# M652A.net
KiCad netlist of a schematic drawn in EAGLE
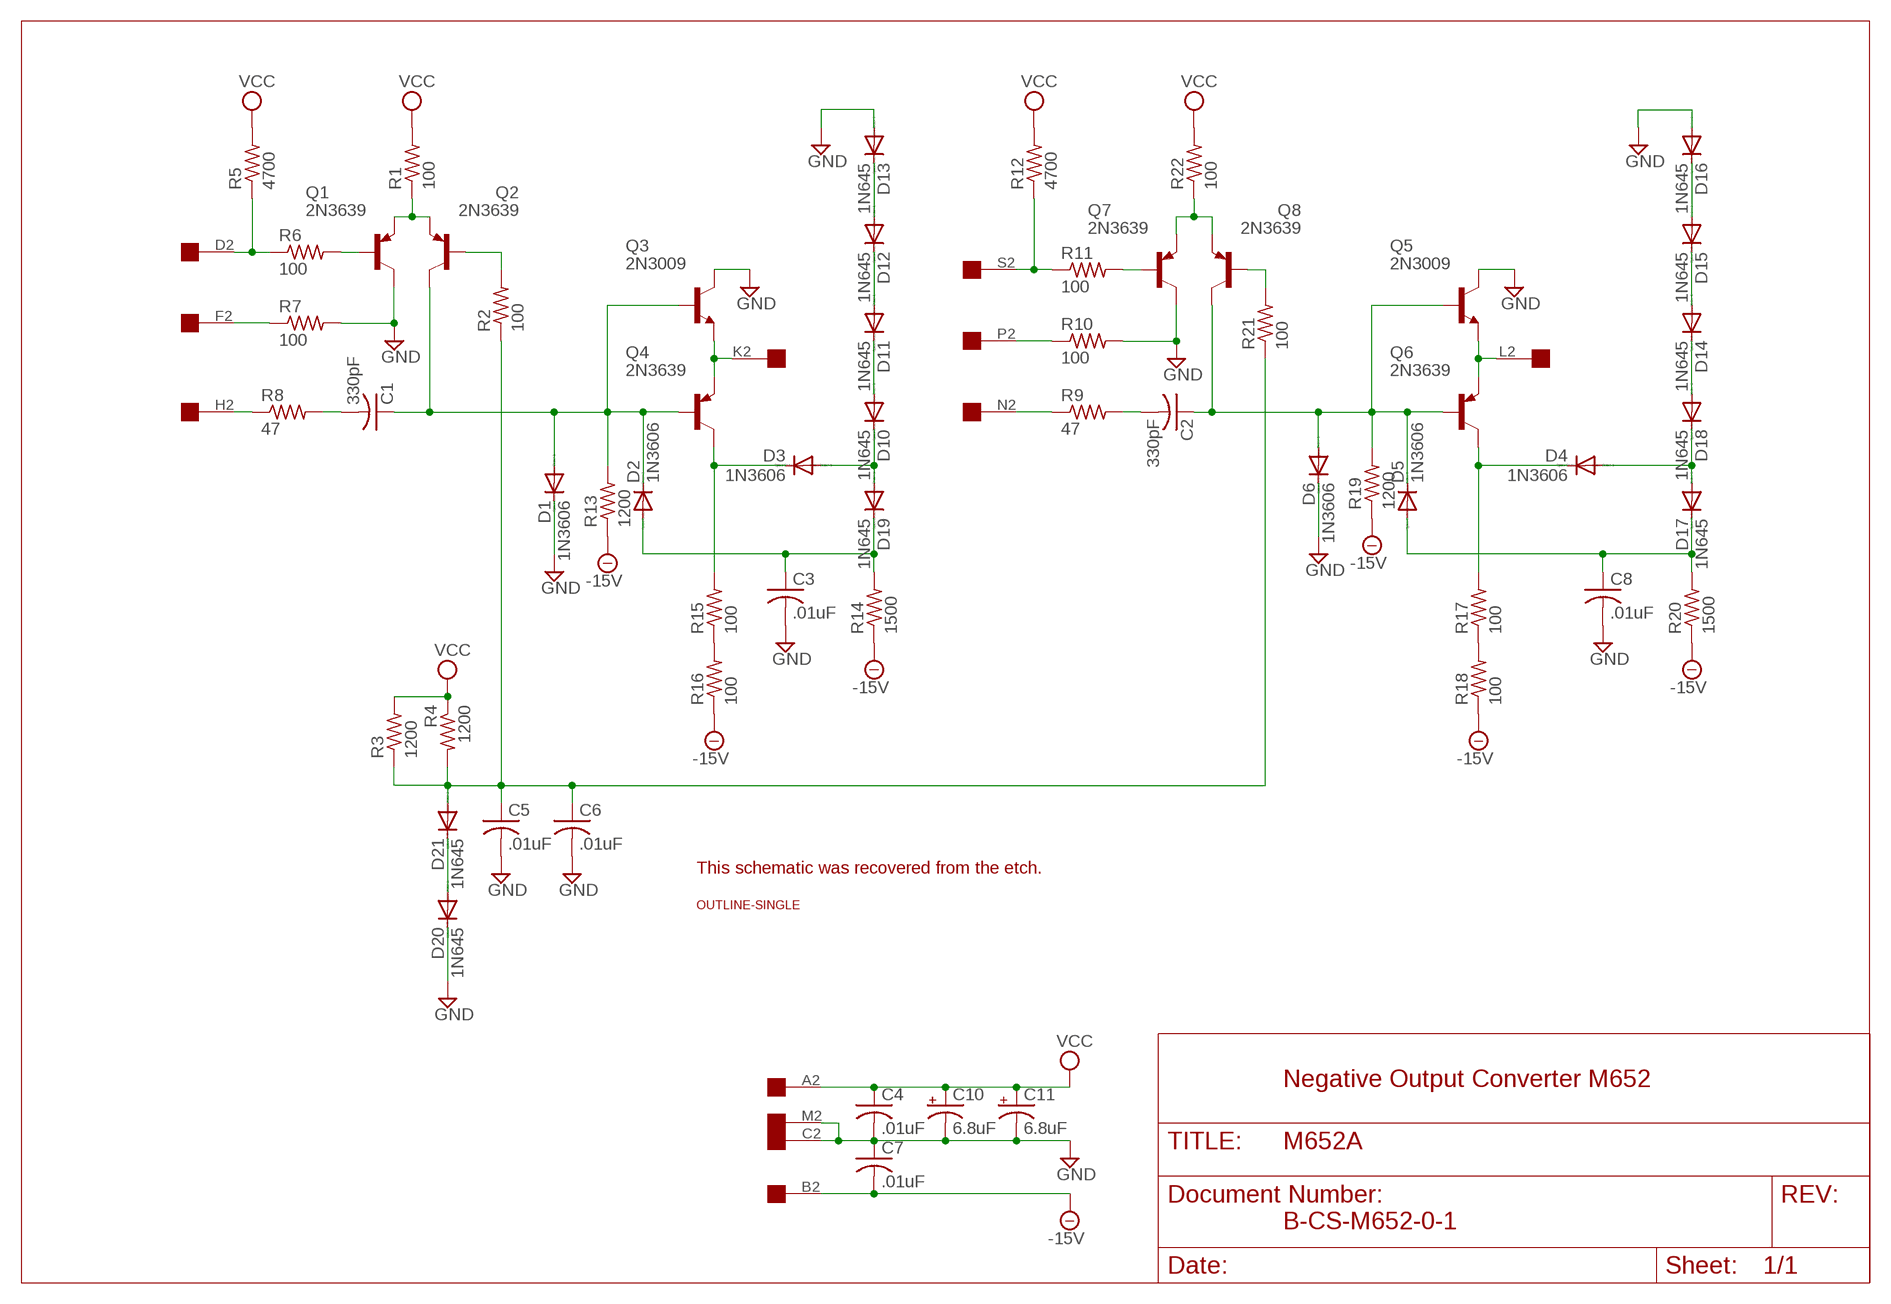
[diagram p0: schematic, sheet 1]

(export (version "E")
  (design (tool "Eeschema 10.0.6"))
  (components
    (comp (ref "C1")
      (value "330pF")
      (footprint "eagle-import:C150-054X183")
      (libsource (lib "eagle-import") (part "C-US150-054X183"))
    )
    (comp (ref "C2")
      (value "330pF")
      (footprint "eagle-import:C150-054X183")
      (libsource (lib "eagle-import") (part "C-US150-054X183"))
    )
    (comp (ref "C3")
      (value ".01uF")
      (footprint "eagle-import:C050-025X075")
      (libsource (lib "eagle-import") (part "C-US050-025X075"))
    )
    (comp (ref "C4")
      (value ".01uF")
      (footprint "eagle-import:C050-025X075")
      (libsource (lib "eagle-import") (part "C-US050-025X075"))
    )
    (comp (ref "C5")
      (value ".01uF")
      (footprint "eagle-import:C050-025X075")
      (libsource (lib "eagle-import") (part "C-US050-025X075"))
    )
    (comp (ref "C6")
      (value ".01uF")
      (footprint "eagle-import:C050-025X075")
      (libsource (lib "eagle-import") (part "C-US050-025X075"))
    )
    (comp (ref "C7")
      (value ".01uF")
      (footprint "eagle-import:C050-025X075")
      (libsource (lib "eagle-import") (part "C-US050-025X075"))
    )
    (comp (ref "C8")
      (value ".01uF")
      (footprint "eagle-import:C050-025X075")
      (libsource (lib "eagle-import") (part "C-US050-025X075"))
    )
    (comp (ref "C10")
      (value "6.8uF")
      (footprint "eagle-import:E12-4")
      (libsource (lib "eagle-import") (part "CPOL-USE12-4AXIAL"))
    )
    (comp (ref "C11")
      (value "6.8uF")
      (footprint "eagle-import:E12-4")
      (libsource (lib "eagle-import") (part "CPOL-USE12-4AXIAL"))
    )
    (comp (ref "D1")
      (value "1N3606")
      (footprint "eagle-import:DO35-10")
      (libsource (lib "eagle-import") (part "1N4148DO35-10"))
    )
    (comp (ref "D2")
      (value "1N3606")
      (footprint "eagle-import:DO35-10")
      (libsource (lib "eagle-import") (part "1N4148DO35-10"))
    )
    (comp (ref "D3")
      (value "1N3606")
      (footprint "eagle-import:DO35-10")
      (libsource (lib "eagle-import") (part "1N4148DO35-10"))
    )
    (comp (ref "D4")
      (value "1N3606")
      (footprint "eagle-import:DO35-10")
      (libsource (lib "eagle-import") (part "1N4148DO35-10"))
    )
    (comp (ref "D5")
      (value "1N3606")
      (footprint "eagle-import:DO35-10")
      (libsource (lib "eagle-import") (part "1N4148DO35-10"))
    )
    (comp (ref "D6")
      (value "1N3606")
      (footprint "eagle-import:DO35-10")
      (libsource (lib "eagle-import") (part "1N4148DO35-10"))
    )
    (comp (ref "D10")
      (value "1N645")
      (footprint "eagle-import:DO35-10")
      (libsource (lib "eagle-import") (part "1N4148DO35-10"))
    )
    (comp (ref "D11")
      (value "1N645")
      (footprint "eagle-import:DO35-10")
      (libsource (lib "eagle-import") (part "1N4148DO35-10"))
    )
    (comp (ref "D12")
      (value "1N645")
      (footprint "eagle-import:DO35-10")
      (libsource (lib "eagle-import") (part "1N4148DO35-10"))
    )
    (comp (ref "D13")
      (value "1N645")
      (footprint "eagle-import:DO35-10")
      (libsource (lib "eagle-import") (part "1N4148DO35-10"))
    )
    (comp (ref "D14")
      (value "1N645")
      (footprint "eagle-import:DO35-10")
      (libsource (lib "eagle-import") (part "1N4148DO35-10"))
    )
    (comp (ref "D15")
      (value "1N645")
      (footprint "eagle-import:DO35-10")
      (libsource (lib "eagle-import") (part "1N4148DO35-10"))
    )
    (comp (ref "D16")
      (value "1N645")
      (footprint "eagle-import:DO35-10")
      (libsource (lib "eagle-import") (part "1N4148DO35-10"))
    )
    (comp (ref "D17")
      (value "1N645")
      (footprint "eagle-import:DO35-10")
      (libsource (lib "eagle-import") (part "1N4148DO35-10"))
    )
    (comp (ref "D18")
      (value "1N645")
      (footprint "eagle-import:DO35-10")
      (libsource (lib "eagle-import") (part "1N4148DO35-10"))
    )
    (comp (ref "D19")
      (value "1N645")
      (footprint "eagle-import:DO35-10")
      (libsource (lib "eagle-import") (part "1N4148DO35-10"))
    )
    (comp (ref "D20")
      (value "1N645")
      (footprint "eagle-import:DO35-10")
      (libsource (lib "eagle-import") (part "1N4148DO35-10"))
    )
    (comp (ref "D21")
      (value "1N645")
      (footprint "eagle-import:DO35-10")
      (libsource (lib "eagle-import") (part "1N4148DO35-10"))
    )
    (comp (ref "Q1")
      (value "2N3639")
      (footprint "eagle-import:TO39")
      (libsource (lib "eagle-import") (part "2N5415"))
    )
    (comp (ref "Q2")
      (value "2N3639")
      (footprint "eagle-import:TO39")
      (libsource (lib "eagle-import") (part "2N5415"))
    )
    (comp (ref "Q3")
      (value "2N3009")
      (footprint "eagle-import:TO5")
      (libsource (lib "eagle-import") (part "2N2219"))
    )
    (comp (ref "Q4")
      (value "2N3639")
      (footprint "eagle-import:TO39")
      (libsource (lib "eagle-import") (part "2N5415"))
    )
    (comp (ref "Q5")
      (value "2N3009")
      (footprint "eagle-import:TO5")
      (libsource (lib "eagle-import") (part "2N2219"))
    )
    (comp (ref "Q6")
      (value "2N3639")
      (footprint "eagle-import:TO39")
      (libsource (lib "eagle-import") (part "2N5415"))
    )
    (comp (ref "Q7")
      (value "2N3639")
      (footprint "eagle-import:TO39")
      (libsource (lib "eagle-import") (part "2N5415"))
    )
    (comp (ref "Q8")
      (value "2N3639")
      (footprint "eagle-import:TO39")
      (libsource (lib "eagle-import") (part "2N5415"))
    )
    (comp (ref "R1")
      (value "100")
      (footprint "eagle-import:0207_10")
      (libsource (lib "eagle-import") (part "R-US_0207/10"))
    )
    (comp (ref "R2")
      (value "100")
      (footprint "eagle-import:0207_10")
      (libsource (lib "eagle-import") (part "R-US_0207/10"))
    )
    (comp (ref "R3")
      (value "1200")
      (footprint "eagle-import:0207_10")
      (libsource (lib "eagle-import") (part "R-US_0207/10"))
    )
    (comp (ref "R4")
      (value "1200")
      (footprint "eagle-import:0207_10")
      (libsource (lib "eagle-import") (part "R-US_0207/10"))
    )
    (comp (ref "R5")
      (value "4700")
      (footprint "eagle-import:0207_10")
      (libsource (lib "eagle-import") (part "R-US_0207/10"))
    )
    (comp (ref "R6")
      (value "100")
      (footprint "eagle-import:0207_10")
      (libsource (lib "eagle-import") (part "R-US_0207/10"))
    )
    (comp (ref "R7")
      (value "100")
      (footprint "eagle-import:0207_10")
      (libsource (lib "eagle-import") (part "R-US_0207/10"))
    )
    (comp (ref "R8")
      (value "47")
      (footprint "eagle-import:0207_10")
      (libsource (lib "eagle-import") (part "R-US_0207/10"))
    )
    (comp (ref "R9")
      (value "47")
      (footprint "eagle-import:0207_10")
      (libsource (lib "eagle-import") (part "R-US_0207/10"))
    )
    (comp (ref "R10")
      (value "100")
      (footprint "eagle-import:0207_10")
      (libsource (lib "eagle-import") (part "R-US_0207/10"))
    )
    (comp (ref "R11")
      (value "100")
      (footprint "eagle-import:0207_10")
      (libsource (lib "eagle-import") (part "R-US_0207/10"))
    )
    (comp (ref "R12")
      (value "4700")
      (footprint "eagle-import:0207_10")
      (libsource (lib "eagle-import") (part "R-US_0207/10"))
    )
    (comp (ref "R13")
      (value "1200")
      (footprint "eagle-import:0207_10")
      (libsource (lib "eagle-import") (part "R-US_0207/10"))
    )
    (comp (ref "R14")
      (value "1500")
      (footprint "eagle-import:0207_10")
      (libsource (lib "eagle-import") (part "R-US_0207/10"))
    )
    (comp (ref "R15")
      (value "100")
      (footprint "eagle-import:0207_10")
      (libsource (lib "eagle-import") (part "R-US_0207/10"))
    )
    (comp (ref "R16")
      (value "100")
      (footprint "eagle-import:0207_10")
      (libsource (lib "eagle-import") (part "R-US_0207/10"))
    )
    (comp (ref "R17")
      (value "100")
      (footprint "eagle-import:0207_10")
      (libsource (lib "eagle-import") (part "R-US_0207/10"))
    )
    (comp (ref "R18")
      (value "100")
      (footprint "eagle-import:0207_10")
      (libsource (lib "eagle-import") (part "R-US_0207/10"))
    )
    (comp (ref "R19")
      (value "1200")
      (footprint "eagle-import:0207_10")
      (libsource (lib "eagle-import") (part "R-US_0207/10"))
    )
    (comp (ref "R20")
      (value "1500")
      (footprint "eagle-import:0207_10")
      (libsource (lib "eagle-import") (part "R-US_0207/10"))
    )
    (comp (ref "R21")
      (value "100")
      (footprint "eagle-import:0207_10")
      (libsource (lib "eagle-import") (part "R-US_0207/10"))
    )
    (comp (ref "R22")
      (value "100")
      (footprint "eagle-import:0207_10")
      (libsource (lib "eagle-import") (part "R-US_0207/10"))
    )
    (comp (ref "U$1")
      (value "OUTLINE-SINGLE")
      (footprint "eagle-import:SINGLE")
      (libsource (lib "eagle-import") (part "OUTLINE-SINGLE"))
    )
    (comp (ref "U$3")
      (value "EDGE-1")
      (footprint "eagle-import:EDGE-CON1")
      (libsource (lib "eagle-import") (part "EDGE-1"))
    )
  )
  (nets
    (net (code "1") (name "-15V") (class "Default")
      (node (ref "C7") (pin "2") (pinfunction "2_2") (pintype "passive"))
      (node (ref "R13") (pin "1") (pinfunction "1_1") (pintype "passive"))
      (node (ref "R14") (pin "1") (pinfunction "1_1") (pintype "passive"))
      (node (ref "R16") (pin "1") (pinfunction "1_1") (pintype "passive"))
      (node (ref "R18") (pin "1") (pinfunction "1_1") (pintype "passive"))
      (node (ref "R19") (pin "1") (pinfunction "1_1") (pintype "passive"))
      (node (ref "R20") (pin "1") (pinfunction "1_1") (pintype "passive"))
      (node (ref "U$3") (pin "B2") (pinfunction "1_B2") (pintype "bidirectional"))
    )
    (net (code "2") (name "GND") (class "Default")
      (node (ref "C10") (pin "-") (pinfunction "-_-") (pintype "passive"))
      (node (ref "C11") (pin "-") (pinfunction "-_-") (pintype "passive"))
      (node (ref "C3") (pin "2") (pinfunction "2_2") (pintype "passive"))
      (node (ref "C4") (pin "2") (pinfunction "2_2") (pintype "passive"))
      (node (ref "C5") (pin "2") (pinfunction "2_2") (pintype "passive"))
      (node (ref "C6") (pin "2") (pinfunction "2_2") (pintype "passive"))
      (node (ref "C7") (pin "1") (pinfunction "1_1") (pintype "passive"))
      (node (ref "C8") (pin "2") (pinfunction "2_2") (pintype "passive"))
      (node (ref "D1") (pin "C") (pinfunction "C_C") (pintype "passive"))
      (node (ref "D13") (pin "A") (pinfunction "A_A") (pintype "passive"))
      (node (ref "D16") (pin "A") (pinfunction "A_A") (pintype "passive"))
      (node (ref "D20") (pin "C") (pinfunction "C_C") (pintype "passive"))
      (node (ref "D6") (pin "C") (pinfunction "C_C") (pintype "passive"))
      (node (ref "Q1") (pin "3") (pinfunction "C_3") (pintype "passive"))
      (node (ref "Q3") (pin "3") (pinfunction "C_3") (pintype "passive"))
      (node (ref "Q5") (pin "3") (pinfunction "C_3") (pintype "passive"))
      (node (ref "Q7") (pin "3") (pinfunction "C_3") (pintype "passive"))
      (node (ref "R10") (pin "2") (pinfunction "2_2") (pintype "passive"))
      (node (ref "R7") (pin "2") (pinfunction "2_2") (pintype "passive"))
      (node (ref "U$3") (pin "C2") (pinfunction "1_C2") (pintype "bidirectional"))
      (node (ref "U$3") (pin "M2") (pinfunction "1_M2") (pintype "bidirectional"))
    )
    (net (code "3") (name "Net-(C1-Pad2)") (class "Default")
      (node (ref "C1") (pin "2") (pinfunction "2_2") (pintype "passive"))
      (node (ref "R8") (pin "2") (pinfunction "2_2") (pintype "passive"))
    )
    (net (code "4") (name "Net-(C2-Pad2)") (class "Default")
      (node (ref "C2") (pin "2") (pinfunction "2_2") (pintype "passive"))
      (node (ref "R9") (pin "2") (pinfunction "2_2") (pintype "passive"))
    )
    (net (code "5") (name "Net-(C3-Pad1)") (class "Default")
      (node (ref "C3") (pin "1") (pinfunction "1_1") (pintype "passive"))
      (node (ref "D19") (pin "C") (pinfunction "C_C") (pintype "passive"))
      (node (ref "D2") (pin "A") (pinfunction "A_A") (pintype "passive"))
      (node (ref "R14") (pin "2") (pinfunction "2_2") (pintype "passive"))
    )
    (net (code "6") (name "Net-(C5-Pad1)") (class "Default")
      (node (ref "C5") (pin "1") (pinfunction "1_1") (pintype "passive"))
      (node (ref "C6") (pin "1") (pinfunction "1_1") (pintype "passive"))
      (node (ref "D21") (pin "A") (pinfunction "A_A") (pintype "passive"))
      (node (ref "R2") (pin "1") (pinfunction "1_1") (pintype "passive"))
      (node (ref "R21") (pin "1") (pinfunction "1_1") (pintype "passive"))
      (node (ref "R3") (pin "1") (pinfunction "1_1") (pintype "passive"))
      (node (ref "R4") (pin "2") (pinfunction "2_2") (pintype "passive"))
    )
    (net (code "7") (name "Net-(C8-Pad1)") (class "Default")
      (node (ref "C8") (pin "1") (pinfunction "1_1") (pintype "passive"))
      (node (ref "D17") (pin "C") (pinfunction "C_C") (pintype "passive"))
      (node (ref "D5") (pin "A") (pinfunction "A_A") (pintype "passive"))
      (node (ref "R20") (pin "2") (pinfunction "2_2") (pintype "passive"))
    )
    (net (code "8") (name "Net-(D10-PadA)") (class "Default")
      (node (ref "D10") (pin "A") (pinfunction "A_A") (pintype "passive"))
      (node (ref "D11") (pin "C") (pinfunction "C_C") (pintype "passive"))
    )
    (net (code "9") (name "Net-(D10-PadC)") (class "Default")
      (node (ref "D10") (pin "C") (pinfunction "C_C") (pintype "passive"))
      (node (ref "D19") (pin "A") (pinfunction "A_A") (pintype "passive"))
      (node (ref "D3") (pin "A") (pinfunction "A_A") (pintype "passive"))
    )
    (net (code "10") (name "Net-(D11-PadA)") (class "Default")
      (node (ref "D11") (pin "A") (pinfunction "A_A") (pintype "passive"))
      (node (ref "D12") (pin "C") (pinfunction "C_C") (pintype "passive"))
    )
    (net (code "11") (name "Net-(D12-PadA)") (class "Default")
      (node (ref "D12") (pin "A") (pinfunction "A_A") (pintype "passive"))
      (node (ref "D13") (pin "C") (pinfunction "C_C") (pintype "passive"))
    )
    (net (code "12") (name "Net-(D14-PadA)") (class "Default")
      (node (ref "D14") (pin "A") (pinfunction "A_A") (pintype "passive"))
      (node (ref "D15") (pin "C") (pinfunction "C_C") (pintype "passive"))
    )
    (net (code "13") (name "Net-(D14-PadC)") (class "Default")
      (node (ref "D14") (pin "C") (pinfunction "C_C") (pintype "passive"))
      (node (ref "D18") (pin "A") (pinfunction "A_A") (pintype "passive"))
    )
    (net (code "14") (name "Net-(D15-PadA)") (class "Default")
      (node (ref "D15") (pin "A") (pinfunction "A_A") (pintype "passive"))
      (node (ref "D16") (pin "C") (pinfunction "C_C") (pintype "passive"))
    )
    (net (code "15") (name "Net-(D17-PadA)") (class "Default")
      (node (ref "D17") (pin "A") (pinfunction "A_A") (pintype "passive"))
      (node (ref "D18") (pin "C") (pinfunction "C_C") (pintype "passive"))
      (node (ref "D4") (pin "A") (pinfunction "A_A") (pintype "passive"))
    )
    (net (code "16") (name "Net-(D20-PadA)") (class "Default")
      (node (ref "D20") (pin "A") (pinfunction "A_A") (pintype "passive"))
      (node (ref "D21") (pin "C") (pinfunction "C_C") (pintype "passive"))
    )
    (net (code "17") (name "Net-(Q1-B)") (class "Default")
      (node (ref "Q1") (pin "2") (pinfunction "B_2") (pintype "passive"))
      (node (ref "R6") (pin "2") (pinfunction "2_2") (pintype "passive"))
    )
    (net (code "18") (name "Net-(Q1-E)") (class "Default")
      (node (ref "Q1") (pin "1") (pinfunction "E_1") (pintype "passive"))
      (node (ref "Q2") (pin "1") (pinfunction "E_1") (pintype "passive"))
      (node (ref "R1") (pin "1") (pinfunction "1_1") (pintype "passive"))
    )
    (net (code "19") (name "Net-(Q2-B)") (class "Default")
      (node (ref "Q2") (pin "2") (pinfunction "B_2") (pintype "passive"))
      (node (ref "R2") (pin "2") (pinfunction "2_2") (pintype "passive"))
    )
    (net (code "20") (name "Net-(Q2-C)") (class "Default")
      (node (ref "C1") (pin "1") (pinfunction "1_1") (pintype "passive"))
      (node (ref "D1") (pin "A") (pinfunction "A_A") (pintype "passive"))
      (node (ref "D2") (pin "C") (pinfunction "C_C") (pintype "passive"))
      (node (ref "Q2") (pin "3") (pinfunction "C_3") (pintype "passive"))
      (node (ref "Q3") (pin "2") (pinfunction "B_2") (pintype "passive"))
      (node (ref "Q4") (pin "2") (pinfunction "B_2") (pintype "passive"))
      (node (ref "R13") (pin "2") (pinfunction "2_2") (pintype "passive"))
    )
    (net (code "21") (name "Net-(Q3-E)") (class "Default")
      (node (ref "Q3") (pin "1") (pinfunction "E_1") (pintype "passive"))
      (node (ref "Q4") (pin "1") (pinfunction "E_1") (pintype "passive"))
      (node (ref "U$3") (pin "K2") (pinfunction "1_K2") (pintype "bidirectional"))
    )
    (net (code "22") (name "Net-(Q4-C)") (class "Default")
      (node (ref "D3") (pin "C") (pinfunction "C_C") (pintype "passive"))
      (node (ref "Q4") (pin "3") (pinfunction "C_3") (pintype "passive"))
      (node (ref "R15") (pin "2") (pinfunction "2_2") (pintype "passive"))
    )
    (net (code "23") (name "Net-(Q5-B)") (class "Default")
      (node (ref "C2") (pin "1") (pinfunction "1_1") (pintype "passive"))
      (node (ref "D5") (pin "C") (pinfunction "C_C") (pintype "passive"))
      (node (ref "D6") (pin "A") (pinfunction "A_A") (pintype "passive"))
      (node (ref "Q5") (pin "2") (pinfunction "B_2") (pintype "passive"))
      (node (ref "Q6") (pin "2") (pinfunction "B_2") (pintype "passive"))
      (node (ref "Q8") (pin "3") (pinfunction "C_3") (pintype "passive"))
      (node (ref "R19") (pin "2") (pinfunction "2_2") (pintype "passive"))
    )
    (net (code "24") (name "Net-(Q5-E)") (class "Default")
      (node (ref "Q5") (pin "1") (pinfunction "E_1") (pintype "passive"))
      (node (ref "Q6") (pin "1") (pinfunction "E_1") (pintype "passive"))
      (node (ref "U$3") (pin "L2") (pinfunction "1_L2") (pintype "bidirectional"))
    )
    (net (code "25") (name "Net-(Q6-C)") (class "Default")
      (node (ref "D4") (pin "C") (pinfunction "C_C") (pintype "passive"))
      (node (ref "Q6") (pin "3") (pinfunction "C_3") (pintype "passive"))
      (node (ref "R17") (pin "2") (pinfunction "2_2") (pintype "passive"))
    )
    (net (code "26") (name "Net-(Q7-B)") (class "Default")
      (node (ref "Q7") (pin "2") (pinfunction "B_2") (pintype "passive"))
      (node (ref "R11") (pin "2") (pinfunction "2_2") (pintype "passive"))
    )
    (net (code "27") (name "Net-(Q7-E)") (class "Default")
      (node (ref "Q7") (pin "1") (pinfunction "E_1") (pintype "passive"))
      (node (ref "Q8") (pin "1") (pinfunction "E_1") (pintype "passive"))
      (node (ref "R22") (pin "1") (pinfunction "1_1") (pintype "passive"))
    )
    (net (code "28") (name "Net-(Q8-B)") (class "Default")
      (node (ref "Q8") (pin "2") (pinfunction "B_2") (pintype "passive"))
      (node (ref "R21") (pin "2") (pinfunction "2_2") (pintype "passive"))
    )
    (net (code "29") (name "Net-(R15-Pad1)") (class "Default")
      (node (ref "R15") (pin "1") (pinfunction "1_1") (pintype "passive"))
      (node (ref "R16") (pin "2") (pinfunction "2_2") (pintype "passive"))
    )
    (net (code "30") (name "Net-(R17-Pad1)") (class "Default")
      (node (ref "R17") (pin "1") (pinfunction "1_1") (pintype "passive"))
      (node (ref "R18") (pin "2") (pinfunction "2_2") (pintype "passive"))
    )
    (net (code "31") (name "Net-(U$3D-1)") (class "Default")
      (node (ref "R5") (pin "1") (pinfunction "1_1") (pintype "passive"))
      (node (ref "R6") (pin "1") (pinfunction "1_1") (pintype "passive"))
      (node (ref "U$3") (pin "D2") (pinfunction "1_D2") (pintype "bidirectional"))
    )
    (net (code "32") (name "Net-(U$3F-1)") (class "Default")
      (node (ref "R7") (pin "1") (pinfunction "1_1") (pintype "passive"))
      (node (ref "U$3") (pin "F2") (pinfunction "1_F2") (pintype "bidirectional"))
    )
    (net (code "33") (name "Net-(U$3G-1)") (class "Default")
      (node (ref "R8") (pin "1") (pinfunction "1_1") (pintype "passive"))
      (node (ref "U$3") (pin "H2") (pinfunction "1_H2") (pintype "bidirectional"))
    )
    (net (code "34") (name "Net-(U$3L-1)") (class "Default")
      (node (ref "R9") (pin "1") (pinfunction "1_1") (pintype "passive"))
      (node (ref "U$3") (pin "N2") (pinfunction "1_N2") (pintype "bidirectional"))
    )
    (net (code "35") (name "Net-(U$3M-1)") (class "Default")
      (node (ref "R10") (pin "1") (pinfunction "1_1") (pintype "passive"))
      (node (ref "U$3") (pin "P2") (pinfunction "1_P2") (pintype "bidirectional"))
    )
    (net (code "36") (name "Net-(U$3O-1)") (class "Default")
      (node (ref "R11") (pin "1") (pinfunction "1_1") (pintype "passive"))
      (node (ref "R12") (pin "1") (pinfunction "1_1") (pintype "passive"))
      (node (ref "U$3") (pin "S2") (pinfunction "1_S2") (pintype "bidirectional"))
    )
    (net (code "37") (name "VCC") (class "Default")
      (node (ref "C10") (pin "+") (pinfunction "+_+") (pintype "passive"))
      (node (ref "C11") (pin "+") (pinfunction "+_+") (pintype "passive"))
      (node (ref "C4") (pin "1") (pinfunction "1_1") (pintype "passive"))
      (node (ref "R1") (pin "2") (pinfunction "2_2") (pintype "passive"))
      (node (ref "R12") (pin "2") (pinfunction "2_2") (pintype "passive"))
      (node (ref "R22") (pin "2") (pinfunction "2_2") (pintype "passive"))
      (node (ref "R3") (pin "2") (pinfunction "2_2") (pintype "passive"))
      (node (ref "R4") (pin "1") (pinfunction "1_1") (pintype "passive"))
      (node (ref "R5") (pin "2") (pinfunction "2_2") (pintype "passive"))
      (node (ref "U$3") (pin "A2") (pinfunction "1_A2") (pintype "bidirectional"))
    )
  )
)
